# controller.net
KiCad netlist of a schematic drawn in EAGLE
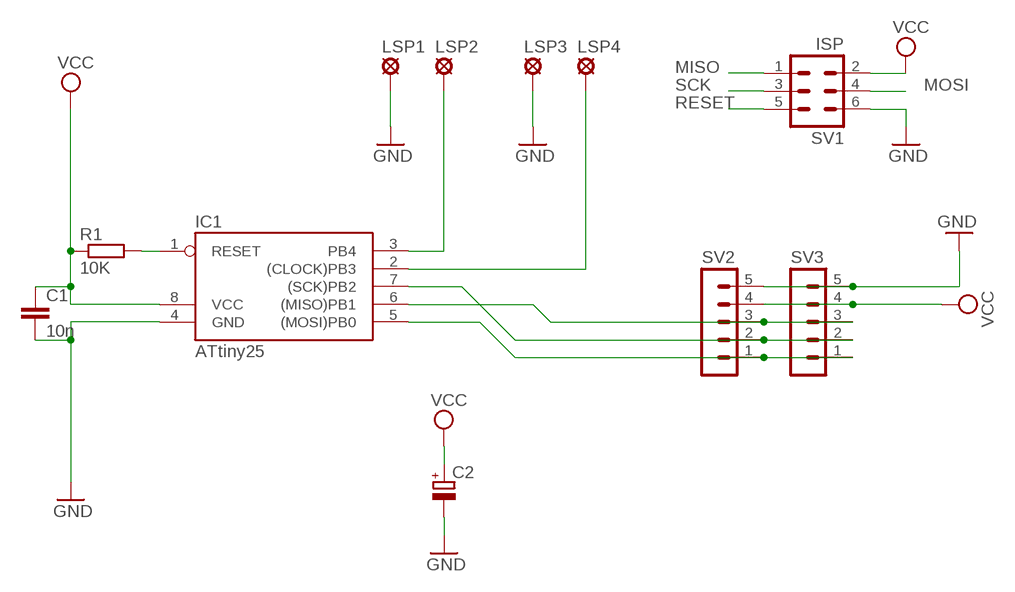
[diagram p0: schematic, sheet 1]

(export (version "E")
  (design (tool "Eeschema 10.0.6"))
  (components
    (comp (ref "C1")
      (value "10n")
      (footprint "eagle-import:C025-024X044")
      (libsource (lib "eagle-import") (part "C-EU025-024X044"))
    )
    (comp (ref "C2")
      (value "CPOL-EUE2.5-6")
      (footprint "eagle-import:E2,5-6")
      (libsource (lib "eagle-import") (part "CPOL-EUE2.5-6"))
    )
    (comp (ref "IC1")
      (value "ATtiny25")
      (footprint "eagle-import:DIL08")
      (libsource (lib "eagle-import") (part "AT902343PS"))
    )
    (comp (ref "LSP1")
      (value "SE11")
      (footprint "eagle-import:SE11")
      (libsource (lib "eagle-import") (part "SE11"))
    )
    (comp (ref "LSP2")
      (value "SE11")
      (footprint "eagle-import:SE11")
      (libsource (lib "eagle-import") (part "SE11"))
    )
    (comp (ref "LSP3")
      (value "SE11")
      (footprint "eagle-import:SE11")
      (libsource (lib "eagle-import") (part "SE11"))
    )
    (comp (ref "LSP4")
      (value "SE11")
      (footprint "eagle-import:SE11")
      (libsource (lib "eagle-import") (part "SE11"))
    )
    (comp (ref "R1")
      (value "10K")
      (footprint "eagle-import:0207_7")
      (libsource (lib "eagle-import") (part "R-EU_0207/7"))
    )
    (comp (ref "SV1")
      (value "ISP")
      (footprint "eagle-import:MA03-2")
      (libsource (lib "eagle-import") (part "MA03-2"))
    )
    (comp (ref "SV2")
      (value "MA05-1")
      (footprint "eagle-import:MA05-1")
      (libsource (lib "eagle-import") (part "MA05-1"))
    )
    (comp (ref "SV3")
      (value "MA05-1")
      (footprint "eagle-import:MA05-1")
      (libsource (lib "eagle-import") (part "MA05-1"))
    )
  )
  (nets
    (net (code "1") (name "/MISO") (class "Default")
      (node (ref "IC1") (pin "6") (pinfunction "(MISO)PB1_6") (pintype "bidirectional"))
      (node (ref "SV1") (pin "1") (pinfunction "1_1") (pintype "passive"))
      (node (ref "SV2") (pin "3") (pinfunction "3_3") (pintype "passive"))
      (node (ref "SV3") (pin "3") (pinfunction "3_3") (pintype "passive"))
    )
    (net (code "2") (name "/MOSI") (class "Default")
      (node (ref "IC1") (pin "5") (pinfunction "(MOSI)PB0_5") (pintype "bidirectional"))
      (node (ref "SV1") (pin "4") (pinfunction "4_4") (pintype "passive"))
      (node (ref "SV2") (pin "1") (pinfunction "1_1") (pintype "passive"))
      (node (ref "SV3") (pin "1") (pinfunction "1_1") (pintype "passive"))
    )
    (net (code "3") (name "/RESET") (class "Default")
      (node (ref "IC1") (pin "1") (pinfunction "RESET_1") (pintype "input"))
      (node (ref "R1") (pin "2") (pinfunction "2_2") (pintype "passive"))
      (node (ref "SV1") (pin "5") (pinfunction "5_5") (pintype "passive"))
    )
    (net (code "4") (name "/SCK") (class "Default")
      (node (ref "IC1") (pin "7") (pinfunction "(SCK)PB2_7") (pintype "bidirectional"))
      (node (ref "SV1") (pin "3") (pinfunction "3_3") (pintype "passive"))
      (node (ref "SV2") (pin "2") (pinfunction "2_2") (pintype "passive"))
      (node (ref "SV3") (pin "2") (pinfunction "2_2") (pintype "passive"))
    )
    (net (code "5") (name "GND") (class "Default")
      (node (ref "C1") (pin "2") (pinfunction "2_2") (pintype "passive"))
      (node (ref "C2") (pin "-") (pinfunction "-_-") (pintype "passive"))
      (node (ref "IC1") (pin "4") (pinfunction "GND_4") (pintype "power_in"))
      (node (ref "LSP1") (pin "MP") (pinfunction "MP_MP") (pintype "passive"))
      (node (ref "LSP3") (pin "MP") (pinfunction "MP_MP") (pintype "passive"))
      (node (ref "SV1") (pin "6") (pinfunction "6_6") (pintype "passive"))
      (node (ref "SV2") (pin "5") (pinfunction "5_5") (pintype "passive"))
      (node (ref "SV3") (pin "5") (pinfunction "5_5") (pintype "passive"))
    )
    (net (code "6") (name "Net-(IC1-(CLOCK)PB3)") (class "Default")
      (node (ref "IC1") (pin "2") (pinfunction "(CLOCK)PB3_2") (pintype "bidirectional"))
      (node (ref "LSP4") (pin "MP") (pinfunction "MP_MP") (pintype "passive"))
    )
    (net (code "7") (name "Net-(IC1-PB4)") (class "Default")
      (node (ref "IC1") (pin "3") (pinfunction "PB4_3") (pintype "bidirectional"))
      (node (ref "LSP2") (pin "MP") (pinfunction "MP_MP") (pintype "passive"))
    )
    (net (code "8") (name "VCC") (class "Default")
      (node (ref "C1") (pin "1") (pinfunction "1_1") (pintype "passive"))
      (node (ref "C2") (pin "+") (pinfunction "+_+") (pintype "passive"))
      (node (ref "IC1") (pin "8") (pinfunction "VCC_8") (pintype "power_in"))
      (node (ref "R1") (pin "1") (pinfunction "1_1") (pintype "passive"))
      (node (ref "SV1") (pin "2") (pinfunction "2_2") (pintype "passive"))
      (node (ref "SV2") (pin "4") (pinfunction "4_4") (pintype "passive"))
      (node (ref "SV3") (pin "4") (pinfunction "4_4") (pintype "passive"))
    )
  )
)
